# FPGA_Power.net
KiCad netlist of a schematic drawn in Altium Designer
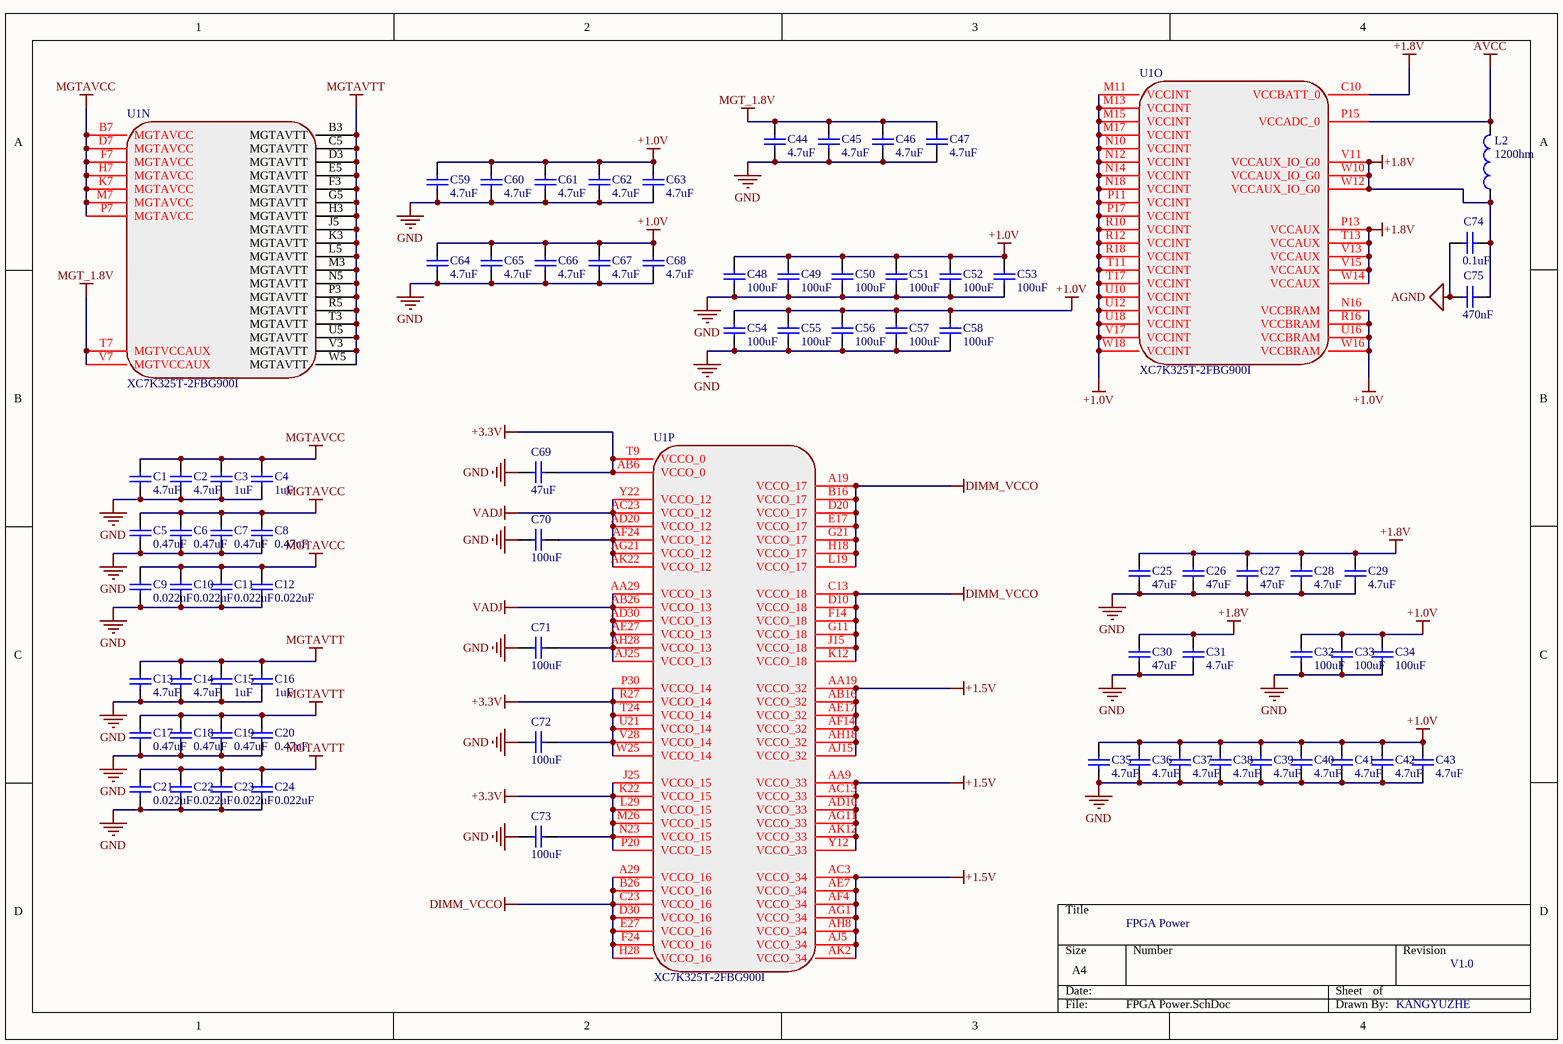
[diagram p0: FPGA Power.SchDoc]

(export (version "E")
  (design (tool "Eeschema 10.0.6"))
  (components
    (comp (ref "C1")
      (value "4.7uF")
      (footprint "0402")
      (description "Capacitor (Semiconductor SIM Model)")
      (fields (field (name "Comment") "Cap Semi") (field (name "PUBLISHER") "Altium Limited"))
      (libsource (lib "Miscellaneous Devices") (part "Cap Semi"))
    )
    (comp (ref "C2")
      (value "4.7uF")
      (footprint "0402")
      (description "Capacitor (Semiconductor SIM Model)")
      (fields (field (name "Comment") "Cap Semi") (field (name "PUBLISHER") "Altium Limited"))
      (libsource (lib "Miscellaneous Devices") (part "Cap Semi"))
    )
    (comp (ref "C3")
      (value "1uF")
      (footprint "0402")
      (description "Capacitor (Semiconductor SIM Model)")
      (fields (field (name "Comment") "Cap Semi") (field (name "PUBLISHER") "Altium Limited"))
      (libsource (lib "Miscellaneous Devices") (part "Cap Semi"))
    )
    (comp (ref "C4")
      (value "1uF")
      (footprint "0402")
      (description "Capacitor (Semiconductor SIM Model)")
      (fields (field (name "Comment") "Cap Semi") (field (name "PUBLISHER") "Altium Limited"))
      (libsource (lib "Miscellaneous Devices") (part "Cap Semi"))
    )
    (comp (ref "C5")
      (value "0.47uF")
      (footprint "0402")
      (description "Capacitor (Semiconductor SIM Model)")
      (fields (field (name "Comment") "Cap Semi") (field (name "PUBLISHER") "Altium Limited"))
      (libsource (lib "Miscellaneous Devices") (part "Cap Semi"))
    )
    (comp (ref "C6")
      (value "0.47uF")
      (footprint "0402")
      (description "Capacitor (Semiconductor SIM Model)")
      (fields (field (name "Comment") "Cap Semi") (field (name "PUBLISHER") "Altium Limited"))
      (libsource (lib "Miscellaneous Devices") (part "Cap Semi"))
    )
    (comp (ref "C7")
      (value "0.47uF")
      (footprint "0402")
      (description "Capacitor (Semiconductor SIM Model)")
      (fields (field (name "Comment") "Cap Semi") (field (name "PUBLISHER") "Altium Limited"))
      (libsource (lib "Miscellaneous Devices") (part "Cap Semi"))
    )
    (comp (ref "C8")
      (value "0.47uF")
      (footprint "0402")
      (description "Capacitor (Semiconductor SIM Model)")
      (fields (field (name "Comment") "Cap Semi") (field (name "PUBLISHER") "Altium Limited"))
      (libsource (lib "Miscellaneous Devices") (part "Cap Semi"))
    )
    (comp (ref "C9")
      (value "0.022uF")
      (footprint "0402")
      (description "Capacitor (Semiconductor SIM Model)")
      (fields (field (name "Comment") "Cap Semi") (field (name "PUBLISHER") "Altium Limited"))
      (libsource (lib "Miscellaneous Devices") (part "Cap Semi"))
    )
    (comp (ref "C10")
      (value "0.022uF")
      (footprint "0402")
      (description "Capacitor (Semiconductor SIM Model)")
      (fields (field (name "Comment") "Cap Semi") (field (name "PUBLISHER") "Altium Limited"))
      (libsource (lib "Miscellaneous Devices") (part "Cap Semi"))
    )
    (comp (ref "C11")
      (value "0.022uF")
      (footprint "0402")
      (description "Capacitor (Semiconductor SIM Model)")
      (fields (field (name "Comment") "Cap Semi") (field (name "PUBLISHER") "Altium Limited"))
      (libsource (lib "Miscellaneous Devices") (part "Cap Semi"))
    )
    (comp (ref "C12")
      (value "0.022uF")
      (footprint "0402")
      (description "Capacitor (Semiconductor SIM Model)")
      (fields (field (name "Comment") "Cap Semi") (field (name "PUBLISHER") "Altium Limited"))
      (libsource (lib "Miscellaneous Devices") (part "Cap Semi"))
    )
    (comp (ref "C13")
      (value "4.7uF")
      (footprint "0402")
      (description "Capacitor (Semiconductor SIM Model)")
      (fields (field (name "Comment") "Cap Semi") (field (name "PUBLISHER") "Altium Limited"))
      (libsource (lib "Miscellaneous Devices") (part "Cap Semi"))
    )
    (comp (ref "C14")
      (value "4.7uF")
      (footprint "0402")
      (description "Capacitor (Semiconductor SIM Model)")
      (fields (field (name "Comment") "Cap Semi") (field (name "PUBLISHER") "Altium Limited"))
      (libsource (lib "Miscellaneous Devices") (part "Cap Semi"))
    )
    (comp (ref "C15")
      (value "1uF")
      (footprint "0402")
      (description "Capacitor (Semiconductor SIM Model)")
      (fields (field (name "Comment") "Cap Semi") (field (name "PUBLISHER") "Altium Limited"))
      (libsource (lib "Miscellaneous Devices") (part "Cap Semi"))
    )
    (comp (ref "C16")
      (value "1uF")
      (footprint "0402")
      (description "Capacitor (Semiconductor SIM Model)")
      (fields (field (name "Comment") "Cap Semi") (field (name "PUBLISHER") "Altium Limited"))
      (libsource (lib "Miscellaneous Devices") (part "Cap Semi"))
    )
    (comp (ref "C17")
      (value "0.47uF")
      (footprint "0402")
      (description "Capacitor (Semiconductor SIM Model)")
      (fields (field (name "Comment") "Cap Semi") (field (name "PUBLISHER") "Altium Limited"))
      (libsource (lib "Miscellaneous Devices") (part "Cap Semi"))
    )
    (comp (ref "C18")
      (value "0.47uF")
      (footprint "0402")
      (description "Capacitor (Semiconductor SIM Model)")
      (fields (field (name "Comment") "Cap Semi") (field (name "PUBLISHER") "Altium Limited"))
      (libsource (lib "Miscellaneous Devices") (part "Cap Semi"))
    )
    (comp (ref "C19")
      (value "0.47uF")
      (footprint "0402")
      (description "Capacitor (Semiconductor SIM Model)")
      (fields (field (name "Comment") "Cap Semi") (field (name "PUBLISHER") "Altium Limited"))
      (libsource (lib "Miscellaneous Devices") (part "Cap Semi"))
    )
    (comp (ref "C20")
      (value "0.47uF")
      (footprint "0402")
      (description "Capacitor (Semiconductor SIM Model)")
      (fields (field (name "Comment") "Cap Semi") (field (name "PUBLISHER") "Altium Limited"))
      (libsource (lib "Miscellaneous Devices") (part "Cap Semi"))
    )
    (comp (ref "C21")
      (value "0.022uF")
      (footprint "0402")
      (description "Capacitor (Semiconductor SIM Model)")
      (fields (field (name "Comment") "Cap Semi") (field (name "PUBLISHER") "Altium Limited"))
      (libsource (lib "Miscellaneous Devices") (part "Cap Semi"))
    )
    (comp (ref "C22")
      (value "0.022uF")
      (footprint "0402")
      (description "Capacitor (Semiconductor SIM Model)")
      (fields (field (name "Comment") "Cap Semi") (field (name "PUBLISHER") "Altium Limited"))
      (libsource (lib "Miscellaneous Devices") (part "Cap Semi"))
    )
    (comp (ref "C23")
      (value "0.022uF")
      (footprint "0402")
      (description "Capacitor (Semiconductor SIM Model)")
      (fields (field (name "Comment") "Cap Semi") (field (name "PUBLISHER") "Altium Limited"))
      (libsource (lib "Miscellaneous Devices") (part "Cap Semi"))
    )
    (comp (ref "C24")
      (value "0.022uF")
      (footprint "0402")
      (description "Capacitor (Semiconductor SIM Model)")
      (fields (field (name "Comment") "Cap Semi") (field (name "PUBLISHER") "Altium Limited"))
      (libsource (lib "Miscellaneous Devices") (part "Cap Semi"))
    )
    (comp (ref "C25")
      (value "47uF")
      (footprint "0402")
      (description "Capacitor (Semiconductor SIM Model)")
      (fields (field (name "Comment") "Cap Semi") (field (name "PUBLISHER") "Altium Limited"))
      (libsource (lib "Miscellaneous Devices") (part "Cap Semi"))
    )
    (comp (ref "C26")
      (value "47uF")
      (footprint "0402")
      (description "Capacitor (Semiconductor SIM Model)")
      (fields (field (name "Comment") "Cap Semi") (field (name "PUBLISHER") "Altium Limited"))
      (libsource (lib "Miscellaneous Devices") (part "Cap Semi"))
    )
    (comp (ref "C27")
      (value "47uF")
      (footprint "0402")
      (description "Capacitor (Semiconductor SIM Model)")
      (fields (field (name "Comment") "Cap Semi") (field (name "PUBLISHER") "Altium Limited"))
      (libsource (lib "Miscellaneous Devices") (part "Cap Semi"))
    )
    (comp (ref "C28")
      (value "4.7uF")
      (footprint "0402")
      (description "Capacitor (Semiconductor SIM Model)")
      (fields (field (name "Comment") "Cap Semi") (field (name "PUBLISHER") "Altium Limited"))
      (libsource (lib "Miscellaneous Devices") (part "Cap Semi"))
    )
    (comp (ref "C29")
      (value "4.7uF")
      (footprint "0402")
      (description "Capacitor (Semiconductor SIM Model)")
      (fields (field (name "Comment") "Cap Semi") (field (name "PUBLISHER") "Altium Limited"))
      (libsource (lib "Miscellaneous Devices") (part "Cap Semi"))
    )
    (comp (ref "C30")
      (value "47uF")
      (footprint "0402")
      (description "Capacitor (Semiconductor SIM Model)")
      (fields (field (name "Comment") "Cap Semi") (field (name "PUBLISHER") "Altium Limited"))
      (libsource (lib "Miscellaneous Devices") (part "Cap Semi"))
    )
    (comp (ref "C31")
      (value "4.7uF")
      (footprint "0402")
      (description "Capacitor (Semiconductor SIM Model)")
      (fields (field (name "Comment") "Cap Semi") (field (name "PUBLISHER") "Altium Limited"))
      (libsource (lib "Miscellaneous Devices") (part "Cap Semi"))
    )
    (comp (ref "C32")
      (value "100uF")
      (footprint "0402")
      (description "Capacitor (Semiconductor SIM Model)")
      (fields (field (name "Comment") "Cap Semi") (field (name "PUBLISHER") "Altium Limited"))
      (libsource (lib "Miscellaneous Devices") (part "Cap Semi"))
    )
    (comp (ref "C33")
      (value "100uF")
      (footprint "0402")
      (description "Capacitor (Semiconductor SIM Model)")
      (fields (field (name "Comment") "Cap Semi") (field (name "PUBLISHER") "Altium Limited"))
      (libsource (lib "Miscellaneous Devices") (part "Cap Semi"))
    )
    (comp (ref "C34")
      (value "100uF")
      (footprint "0402")
      (description "Capacitor (Semiconductor SIM Model)")
      (fields (field (name "Comment") "Cap Semi") (field (name "PUBLISHER") "Altium Limited"))
      (libsource (lib "Miscellaneous Devices") (part "Cap Semi"))
    )
    (comp (ref "C35")
      (value "4.7uF")
      (footprint "0402")
      (description "Capacitor (Semiconductor SIM Model)")
      (fields (field (name "Comment") "Cap Semi") (field (name "PUBLISHER") "Altium Limited"))
      (libsource (lib "Miscellaneous Devices") (part "Cap Semi"))
    )
    (comp (ref "C36")
      (value "4.7uF")
      (footprint "0402")
      (description "Capacitor (Semiconductor SIM Model)")
      (fields (field (name "Comment") "Cap Semi") (field (name "PUBLISHER") "Altium Limited"))
      (libsource (lib "Miscellaneous Devices") (part "Cap Semi"))
    )
    (comp (ref "C37")
      (value "4.7uF")
      (footprint "0402")
      (description "Capacitor (Semiconductor SIM Model)")
      (fields (field (name "Comment") "Cap Semi") (field (name "PUBLISHER") "Altium Limited"))
      (libsource (lib "Miscellaneous Devices") (part "Cap Semi"))
    )
    (comp (ref "C38")
      (value "4.7uF")
      (footprint "0402")
      (description "Capacitor (Semiconductor SIM Model)")
      (fields (field (name "Comment") "Cap Semi") (field (name "PUBLISHER") "Altium Limited"))
      (libsource (lib "Miscellaneous Devices") (part "Cap Semi"))
    )
    (comp (ref "C39")
      (value "4.7uF")
      (footprint "0402")
      (description "Capacitor (Semiconductor SIM Model)")
      (fields (field (name "Comment") "Cap Semi") (field (name "PUBLISHER") "Altium Limited"))
      (libsource (lib "Miscellaneous Devices") (part "Cap Semi"))
    )
    (comp (ref "C40")
      (value "4.7uF")
      (footprint "0402")
      (description "Capacitor (Semiconductor SIM Model)")
      (fields (field (name "Comment") "Cap Semi") (field (name "PUBLISHER") "Altium Limited"))
      (libsource (lib "Miscellaneous Devices") (part "Cap Semi"))
    )
    (comp (ref "C41")
      (value "4.7uF")
      (footprint "0402")
      (description "Capacitor (Semiconductor SIM Model)")
      (fields (field (name "Comment") "Cap Semi") (field (name "PUBLISHER") "Altium Limited"))
      (libsource (lib "Miscellaneous Devices") (part "Cap Semi"))
    )
    (comp (ref "C42")
      (value "4.7uF")
      (footprint "0402")
      (description "Capacitor (Semiconductor SIM Model)")
      (fields (field (name "Comment") "Cap Semi") (field (name "PUBLISHER") "Altium Limited"))
      (libsource (lib "Miscellaneous Devices") (part "Cap Semi"))
    )
    (comp (ref "C43")
      (value "4.7uF")
      (footprint "0402")
      (description "Capacitor (Semiconductor SIM Model)")
      (fields (field (name "Comment") "Cap Semi") (field (name "PUBLISHER") "Altium Limited"))
      (libsource (lib "Miscellaneous Devices") (part "Cap Semi"))
    )
    (comp (ref "C44")
      (value "4.7uF")
      (footprint "0402")
      (description "Capacitor (Semiconductor SIM Model)")
      (fields (field (name "Comment") "Cap Semi") (field (name "PUBLISHER") "Altium Limited"))
      (libsource (lib "Miscellaneous Devices") (part "Cap Semi"))
    )
    (comp (ref "C45")
      (value "4.7uF")
      (footprint "0402")
      (description "Capacitor (Semiconductor SIM Model)")
      (fields (field (name "Comment") "Cap Semi") (field (name "PUBLISHER") "Altium Limited"))
      (libsource (lib "Miscellaneous Devices") (part "Cap Semi"))
    )
    (comp (ref "C46")
      (value "4.7uF")
      (footprint "0402")
      (description "Capacitor (Semiconductor SIM Model)")
      (fields (field (name "Comment") "Cap Semi") (field (name "PUBLISHER") "Altium Limited"))
      (libsource (lib "Miscellaneous Devices") (part "Cap Semi"))
    )
    (comp (ref "C47")
      (value "4.7uF")
      (footprint "0402")
      (description "Capacitor (Semiconductor SIM Model)")
      (fields (field (name "Comment") "Cap Semi") (field (name "PUBLISHER") "Altium Limited"))
      (libsource (lib "Miscellaneous Devices") (part "Cap Semi"))
    )
    (comp (ref "C48")
      (value "100uF")
      (footprint "0402")
      (description "Capacitor (Semiconductor SIM Model)")
      (fields (field (name "Comment") "Cap Semi") (field (name "PUBLISHER") "Altium Limited"))
      (libsource (lib "Miscellaneous Devices") (part "Cap Semi"))
    )
    (comp (ref "C49")
      (value "100uF")
      (footprint "0402")
      (description "Capacitor (Semiconductor SIM Model)")
      (fields (field (name "Comment") "Cap Semi") (field (name "PUBLISHER") "Altium Limited"))
      (libsource (lib "Miscellaneous Devices") (part "Cap Semi"))
    )
    (comp (ref "C50")
      (value "100uF")
      (footprint "0402")
      (description "Capacitor (Semiconductor SIM Model)")
      (fields (field (name "Comment") "Cap Semi") (field (name "PUBLISHER") "Altium Limited"))
      (libsource (lib "Miscellaneous Devices") (part "Cap Semi"))
    )
    (comp (ref "C51")
      (value "100uF")
      (footprint "0402")
      (description "Capacitor (Semiconductor SIM Model)")
      (fields (field (name "Comment") "Cap Semi") (field (name "PUBLISHER") "Altium Limited"))
      (libsource (lib "Miscellaneous Devices") (part "Cap Semi"))
    )
    (comp (ref "C52")
      (value "100uF")
      (footprint "0402")
      (description "Capacitor (Semiconductor SIM Model)")
      (fields (field (name "Comment") "Cap Semi") (field (name "PUBLISHER") "Altium Limited"))
      (libsource (lib "Miscellaneous Devices") (part "Cap Semi"))
    )
    (comp (ref "C53")
      (value "100uF")
      (footprint "0402")
      (description "Capacitor (Semiconductor SIM Model)")
      (fields (field (name "Comment") "Cap Semi") (field (name "PUBLISHER") "Altium Limited"))
      (libsource (lib "Miscellaneous Devices") (part "Cap Semi"))
    )
    (comp (ref "C54")
      (value "100uF")
      (footprint "0402")
      (description "Capacitor (Semiconductor SIM Model)")
      (fields (field (name "Comment") "Cap Semi") (field (name "PUBLISHER") "Altium Limited"))
      (libsource (lib "Miscellaneous Devices") (part "Cap Semi"))
    )
    (comp (ref "C55")
      (value "100uF")
      (footprint "0402")
      (description "Capacitor (Semiconductor SIM Model)")
      (fields (field (name "Comment") "Cap Semi") (field (name "PUBLISHER") "Altium Limited"))
      (libsource (lib "Miscellaneous Devices") (part "Cap Semi"))
    )
    (comp (ref "C56")
      (value "100uF")
      (footprint "0402")
      (description "Capacitor (Semiconductor SIM Model)")
      (fields (field (name "Comment") "Cap Semi") (field (name "PUBLISHER") "Altium Limited"))
      (libsource (lib "Miscellaneous Devices") (part "Cap Semi"))
    )
    (comp (ref "C57")
      (value "100uF")
      (footprint "0402")
      (description "Capacitor (Semiconductor SIM Model)")
      (fields (field (name "Comment") "Cap Semi") (field (name "PUBLISHER") "Altium Limited"))
      (libsource (lib "Miscellaneous Devices") (part "Cap Semi"))
    )
    (comp (ref "C58")
      (value "100uF")
      (footprint "0402")
      (description "Capacitor (Semiconductor SIM Model)")
      (fields (field (name "Comment") "Cap Semi") (field (name "PUBLISHER") "Altium Limited"))
      (libsource (lib "Miscellaneous Devices") (part "Cap Semi"))
    )
    (comp (ref "C59")
      (value "4.7uF")
      (footprint "0402")
      (description "Capacitor (Semiconductor SIM Model)")
      (fields (field (name "Comment") "Cap Semi") (field (name "PUBLISHER") "Altium Limited"))
      (libsource (lib "Miscellaneous Devices") (part "Cap Semi"))
    )
    (comp (ref "C60")
      (value "4.7uF")
      (footprint "0402")
      (description "Capacitor (Semiconductor SIM Model)")
      (fields (field (name "Comment") "Cap Semi") (field (name "PUBLISHER") "Altium Limited"))
      (libsource (lib "Miscellaneous Devices") (part "Cap Semi"))
    )
    (comp (ref "C61")
      (value "4.7uF")
      (footprint "0402")
      (description "Capacitor (Semiconductor SIM Model)")
      (fields (field (name "Comment") "Cap Semi") (field (name "PUBLISHER") "Altium Limited"))
      (libsource (lib "Miscellaneous Devices") (part "Cap Semi"))
    )
    (comp (ref "C62")
      (value "4.7uF")
      (footprint "0402")
      (description "Capacitor (Semiconductor SIM Model)")
      (fields (field (name "Comment") "Cap Semi") (field (name "PUBLISHER") "Altium Limited"))
      (libsource (lib "Miscellaneous Devices") (part "Cap Semi"))
    )
    (comp (ref "C63")
      (value "4.7uF")
      (footprint "0402")
      (description "Capacitor (Semiconductor SIM Model)")
      (fields (field (name "Comment") "Cap Semi") (field (name "PUBLISHER") "Altium Limited"))
      (libsource (lib "Miscellaneous Devices") (part "Cap Semi"))
    )
    (comp (ref "C64")
      (value "4.7uF")
      (footprint "0402")
      (description "Capacitor (Semiconductor SIM Model)")
      (fields (field (name "Comment") "Cap Semi") (field (name "PUBLISHER") "Altium Limited"))
      (libsource (lib "Miscellaneous Devices") (part "Cap Semi"))
    )
    (comp (ref "C65")
      (value "4.7uF")
      (footprint "0402")
      (description "Capacitor (Semiconductor SIM Model)")
      (fields (field (name "Comment") "Cap Semi") (field (name "PUBLISHER") "Altium Limited"))
      (libsource (lib "Miscellaneous Devices") (part "Cap Semi"))
    )
    (comp (ref "C66")
      (value "4.7uF")
      (footprint "0402")
      (description "Capacitor (Semiconductor SIM Model)")
      (fields (field (name "Comment") "Cap Semi") (field (name "PUBLISHER") "Altium Limited"))
      (libsource (lib "Miscellaneous Devices") (part "Cap Semi"))
    )
    (comp (ref "C67")
      (value "4.7uF")
      (footprint "0402")
      (description "Capacitor (Semiconductor SIM Model)")
      (fields (field (name "Comment") "Cap Semi") (field (name "PUBLISHER") "Altium Limited"))
      (libsource (lib "Miscellaneous Devices") (part "Cap Semi"))
    )
    (comp (ref "C68")
      (value "4.7uF")
      (footprint "0402")
      (description "Capacitor (Semiconductor SIM Model)")
      (fields (field (name "Comment") "Cap Semi") (field (name "PUBLISHER") "Altium Limited"))
      (libsource (lib "Miscellaneous Devices") (part "Cap Semi"))
    )
    (comp (ref "C69")
      (value "47uF")
      (footprint "0402")
      (description "Capacitor (Semiconductor SIM Model)")
      (fields (field (name "Comment") "Cap Semi") (field (name "PUBLISHER") "Altium Limited"))
      (libsource (lib "Miscellaneous Devices") (part "Cap Semi"))
    )
    (comp (ref "C70")
      (value "100uF")
      (footprint "0402")
      (description "Capacitor (Semiconductor SIM Model)")
      (fields (field (name "Comment") "Cap Semi") (field (name "PUBLISHER") "Altium Limited"))
      (libsource (lib "Miscellaneous Devices") (part "Cap Semi"))
    )
    (comp (ref "C71")
      (value "100uF")
      (footprint "0402")
      (description "Capacitor (Semiconductor SIM Model)")
      (fields (field (name "Comment") "Cap Semi") (field (name "PUBLISHER") "Altium Limited"))
      (libsource (lib "Miscellaneous Devices") (part "Cap Semi"))
    )
    (comp (ref "C72")
      (value "100uF")
      (footprint "0402")
      (description "Capacitor (Semiconductor SIM Model)")
      (fields (field (name "Comment") "Cap Semi") (field (name "PUBLISHER") "Altium Limited"))
      (libsource (lib "Miscellaneous Devices") (part "Cap Semi"))
    )
    (comp (ref "C73")
      (value "100uF")
      (footprint "0402")
      (description "Capacitor (Semiconductor SIM Model)")
      (fields (field (name "Comment") "Cap Semi") (field (name "PUBLISHER") "Altium Limited"))
      (libsource (lib "Miscellaneous Devices") (part "Cap Semi"))
    )
    (comp (ref "C74")
      (value "0.1uF")
      (footprint "0402")
      (description "Capacitor (Semiconductor SIM Model)")
      (fields (field (name "Comment") "Cap Semi") (field (name "PUBLISHER") "Altium Limited"))
      (libsource (lib "Miscellaneous Devices") (part "Cap Semi"))
    )
    (comp (ref "C75")
      (value "470nF")
      (footprint "0402")
      (description "Capacitor (Semiconductor SIM Model)")
      (fields (field (name "Comment") "Cap Semi") (field (name "PUBLISHER") "Altium Limited"))
      (libsource (lib "Miscellaneous Devices") (part "Cap Semi"))
    )
    (comp (ref "L2")
      (value "1200hm")
      (footprint "0402-A")
      (description "Inductor")
      (fields (field (name "PUBLISHER") "Altium Limited"))
      (libsource (lib "Miscellaneous Devices") (part "Inductor"))
    )
    (comp (ref "U1") (value "XC7K325T-2FBG900I") (libsource (lib "Schlib1") (part "XC7K325T-2FBG900I")))
  )
  (nets
    (net (code "1") (name "+1.0V") (class "Default")
      (node (ref "C32") (pin "2") (pinfunction "2_2") (pintype "passive"))
      (node (ref "C33") (pin "2") (pinfunction "2_2") (pintype "passive"))
      (node (ref "C34") (pin "2") (pinfunction "2_2") (pintype "passive"))
      (node (ref "C35") (pin "2") (pinfunction "2_2") (pintype "passive"))
      (node (ref "C36") (pin "2") (pinfunction "2_2") (pintype "passive"))
      (node (ref "C37") (pin "2") (pinfunction "2_2") (pintype "passive"))
      (node (ref "C38") (pin "2") (pinfunction "2_2") (pintype "passive"))
      (node (ref "C39") (pin "2") (pinfunction "2_2") (pintype "passive"))
      (node (ref "C40") (pin "2") (pinfunction "2_2") (pintype "passive"))
      (node (ref "C41") (pin "2") (pinfunction "2_2") (pintype "passive"))
      (node (ref "C42") (pin "2") (pinfunction "2_2") (pintype "passive"))
      (node (ref "C43") (pin "2") (pinfunction "2_2") (pintype "passive"))
      (node (ref "C48") (pin "2") (pinfunction "2_2") (pintype "passive"))
      (node (ref "C49") (pin "2") (pinfunction "2_2") (pintype "passive"))
      (node (ref "C50") (pin "2") (pinfunction "2_2") (pintype "passive"))
      (node (ref "C51") (pin "2") (pinfunction "2_2") (pintype "passive"))
      (node (ref "C52") (pin "2") (pinfunction "2_2") (pintype "passive"))
      (node (ref "C53") (pin "2") (pinfunction "2_2") (pintype "passive"))
      (node (ref "C54") (pin "2") (pinfunction "2_2") (pintype "passive"))
      (node (ref "C55") (pin "2") (pinfunction "2_2") (pintype "passive"))
      (node (ref "C56") (pin "2") (pinfunction "2_2") (pintype "passive"))
      (node (ref "C57") (pin "2") (pinfunction "2_2") (pintype "passive"))
      (node (ref "C58") (pin "2") (pinfunction "2_2") (pintype "passive"))
      (node (ref "C59") (pin "2") (pinfunction "2_2") (pintype "passive"))
      (node (ref "C60") (pin "2") (pinfunction "2_2") (pintype "passive"))
      (node (ref "C61") (pin "2") (pinfunction "2_2") (pintype "passive"))
      (node (ref "C62") (pin "2") (pinfunction "2_2") (pintype "passive"))
      (node (ref "C63") (pin "2") (pinfunction "2_2") (pintype "passive"))
      (node (ref "C64") (pin "2") (pinfunction "2_2") (pintype "passive"))
      (node (ref "C65") (pin "2") (pinfunction "2_2") (pintype "passive"))
      (node (ref "C66") (pin "2") (pinfunction "2_2") (pintype "passive"))
      (node (ref "C67") (pin "2") (pinfunction "2_2") (pintype "passive"))
      (node (ref "C68") (pin "2") (pinfunction "2_2") (pintype "passive"))
      (node (ref "U1") (pin "M11") (pinfunction "VCCINT_M11") (pintype "passive"))
      (node (ref "U1") (pin "M13") (pinfunction "VCCINT_M13") (pintype "passive"))
      (node (ref "U1") (pin "M15") (pinfunction "VCCINT_M15") (pintype "passive"))
      (node (ref "U1") (pin "M17") (pinfunction "VCCINT_M17") (pintype "passive"))
      (node (ref "U1") (pin "N10") (pinfunction "VCCINT_N10") (pintype "passive"))
      (node (ref "U1") (pin "N12") (pinfunction "VCCINT_N12") (pintype "passive"))
      (node (ref "U1") (pin "N14") (pinfunction "VCCINT_N14") (pintype "passive"))
      (node (ref "U1") (pin "N16") (pinfunction "VCCBRAM_N16") (pintype "passive"))
      (node (ref "U1") (pin "N18") (pinfunction "VCCINT_N18") (pintype "passive"))
      (node (ref "U1") (pin "P11") (pinfunction "VCCINT_P11") (pintype "passive"))
      (node (ref "U1") (pin "P17") (pinfunction "VCCINT_P17") (pintype "passive"))
      (node (ref "U1") (pin "R10") (pinfunction "VCCINT_R10") (pintype "passive"))
      (node (ref "U1") (pin "R12") (pinfunction "VCCINT_R12") (pintype "passive"))
      (node (ref "U1") (pin "R16") (pinfunction "VCCBRAM_R16") (pintype "passive"))
      (node (ref "U1") (pin "R18") (pinfunction "VCCINT_R18") (pintype "passive"))
      (node (ref "U1") (pin "T11") (pinfunction "VCCINT_T11") (pintype "passive"))
      (node (ref "U1") (pin "T17") (pinfunction "VCCINT_T17") (pintype "passive"))
      (node (ref "U1") (pin "U10") (pinfunction "VCCINT_U10") (pintype "passive"))
      (node (ref "U1") (pin "U12") (pinfunction "VCCINT_U12") (pintype "passive"))
      (node (ref "U1") (pin "U16") (pinfunction "VCCBRAM_U16") (pintype "passive"))
      (node (ref "U1") (pin "U18") (pinfunction "VCCINT_U18") (pintype "passive"))
      (node (ref "U1") (pin "V17") (pinfunction "VCCINT_V17") (pintype "passive"))
      (node (ref "U1") (pin "W16") (pinfunction "VCCBRAM_W16") (pintype "passive"))
      (node (ref "U1") (pin "W18") (pinfunction "VCCINT_W18") (pintype "passive"))
    )
    (net (code "2") (name "+1.5V") (class "Default")
      (node (ref "U1") (pin "AA19") (pinfunction "VCCO_32_AA19") (pintype "passive"))
      (node (ref "U1") (pin "AA9") (pinfunction "VCCO_33_AA9") (pintype "passive"))
      (node (ref "U1") (pin "AB16") (pinfunction "VCCO_32_AB16") (pintype "passive"))
      (node (ref "U1") (pin "AC13") (pinfunction "VCCO_33_AC13") (pintype "passive"))
      (node (ref "U1") (pin "AC3") (pinfunction "VCCO_34_AC3") (pintype "passive"))
      (node (ref "U1") (pin "AD10") (pinfunction "VCCO_33_AD10") (pintype "passive"))
      (node (ref "U1") (pin "AE17") (pinfunction "VCCO_32_AE17") (pintype "passive"))
      (node (ref "U1") (pin "AE7") (pinfunction "VCCO_34_AE7") (pintype "passive"))
      (node (ref "U1") (pin "AF14") (pinfunction "VCCO_32_AF14") (pintype "passive"))
      (node (ref "U1") (pin "AF4") (pinfunction "VCCO_34_AF4") (pintype "passive"))
      (node (ref "U1") (pin "AG1") (pinfunction "VCCO_34_AG1") (pintype "passive"))
      (node (ref "U1") (pin "AG11") (pinfunction "VCCO_33_AG11") (pintype "passive"))
      (node (ref "U1") (pin "AH18") (pinfunction "VCCO_32_AH18") (pintype "passive"))
      (node (ref "U1") (pin "AH8") (pinfunction "VCCO_34_AH8") (pintype "passive"))
      (node (ref "U1") (pin "AJ15") (pinfunction "VCCO_32_AJ15") (pintype "passive"))
      (node (ref "U1") (pin "AJ5") (pinfunction "VCCO_34_AJ5") (pintype "passive"))
      (node (ref "U1") (pin "AK12") (pinfunction "VCCO_33_AK12") (pintype "passive"))
      (node (ref "U1") (pin "AK2") (pinfunction "VCCO_34_AK2") (pintype "passive"))
      (node (ref "U1") (pin "Y12") (pinfunction "VCCO_33_Y12") (pintype "passive"))
    )
    (net (code "3") (name "+1.8V") (class "Default")
      (node (ref "C25") (pin "2") (pinfunction "2_2") (pintype "passive"))
      (node (ref "C26") (pin "2") (pinfunction "2_2") (pintype "passive"))
      (node (ref "C27") (pin "2") (pinfunction "2_2") (pintype "passive"))
      (node (ref "C28") (pin "2") (pinfunction "2_2") (pintype "passive"))
      (node (ref "C29") (pin "2") (pinfunction "2_2") (pintype "passive"))
      (node (ref "C30") (pin "2") (pinfunction "2_2") (pintype "passive"))
      (node (ref "C31") (pin "2") (pinfunction "2_2") (pintype "passive"))
      (node (ref "C74") (pin "2") (pinfunction "2_2") (pintype "passive"))
      (node (ref "C75") (pin "2") (pinfunction "2_2") (pintype "passive"))
      (node (ref "L2") (pin "1") (pinfunction "1_1") (pintype "passive"))
      (node (ref "U1") (pin "C10") (pinfunction "VCCBATT_0_C10") (pintype "passive"))
      (node (ref "U1") (pin "P13") (pinfunction "VCCAUX_P13") (pintype "passive"))
      (node (ref "U1") (pin "T13") (pinfunction "VCCAUX_T13") (pintype "passive"))
      (node (ref "U1") (pin "V11") (pinfunction "VCCAUX_IO_G0_V11") (pintype "passive"))
      (node (ref "U1") (pin "V13") (pinfunction "VCCAUX_V13") (pintype "passive"))
      (node (ref "U1") (pin "V15") (pinfunction "VCCAUX_V15") (pintype "passive"))
      (node (ref "U1") (pin "W10") (pinfunction "VCCAUX_IO_G0_W10") (pintype "passive"))
      (node (ref "U1") (pin "W12") (pinfunction "VCCAUX_IO_G0_W12") (pintype "passive"))
      (node (ref "U1") (pin "W14") (pinfunction "VCCAUX_W14") (pintype "passive"))
    )
    (net (code "4") (name "+3.3V") (class "Default")
      (node (ref "C69") (pin "2") (pinfunction "2_2") (pintype "passive"))
      (node (ref "C72") (pin "2") (pinfunction "2_2") (pintype "passive"))
      (node (ref "C73") (pin "2") (pinfunction "2_2") (pintype "passive"))
      (node (ref "U1") (pin "AB6") (pinfunction "VCCO_0_AB6") (pintype "passive"))
      (node (ref "U1") (pin "J25") (pinfunction "VCCO_15_J25") (pintype "passive"))
      (node (ref "U1") (pin "K22") (pinfunction "VCCO_15_K22") (pintype "passive"))
      (node (ref "U1") (pin "L29") (pinfunction "VCCO_15_L29") (pintype "passive"))
      (node (ref "U1") (pin "M26") (pinfunction "VCCO_15_M26") (pintype "passive"))
      (node (ref "U1") (pin "N23") (pinfunction "VCCO_15_N23") (pintype "passive"))
      (node (ref "U1") (pin "P20") (pinfunction "VCCO_15_P20") (pintype "passive"))
      (node (ref "U1") (pin "P30") (pinfunction "VCCO_14_P30") (pintype "passive"))
      (node (ref "U1") (pin "R27") (pinfunction "VCCO_14_R27") (pintype "passive"))
      (node (ref "U1") (pin "T24") (pinfunction "VCCO_14_T24") (pintype "passive"))
      (node (ref "U1") (pin "T9") (pinfunction "VCCO_0_T9") (pintype "passive"))
      (node (ref "U1") (pin "U21") (pinfunction "VCCO_14_U21") (pintype "passive"))
      (node (ref "U1") (pin "V28") (pinfunction "VCCO_14_V28") (pintype "passive"))
      (node (ref "U1") (pin "W25") (pinfunction "VCCO_14_W25") (pintype "passive"))
    )
    (net (code "5") (name "AGND") (class "Default")
      (node (ref "C74") (pin "1") (pinfunction "1_1") (pintype "passive"))
      (node (ref "C75") (pin "1") (pinfunction "1_1") (pintype "passive"))
    )
    (net (code "6") (name "AVCC") (class "Default")
      (node (ref "L2") (pin "2") (pinfunction "2_2") (pintype "passive"))
      (node (ref "U1") (pin "P15") (pinfunction "VCCADC_0_P15") (pintype "passive"))
    )
    (net (code "7") (name "DIMM_VCCO") (class "Default")
      (node (ref "U1") (pin "A19") (pinfunction "VCCO_17_A19") (pintype "passive"))
      (node (ref "U1") (pin "A29") (pinfunction "VCCO_16_A29") (pintype "passive"))
      (node (ref "U1") (pin "B16") (pinfunction "VCCO_17_B16") (pintype "passive"))
      (node (ref "U1") (pin "B26") (pinfunction "VCCO_16_B26") (pintype "passive"))
      (node (ref "U1") (pin "C13") (pinfunction "VCCO_18_C13") (pintype "passive"))
      (node (ref "U1") (pin "C23") (pinfunction "VCCO_16_C23") (pintype "passive"))
      (node (ref "U1") (pin "D10") (pinfunction "VCCO_18_D10") (pintype "passive"))
      (node (ref "U1") (pin "D20") (pinfunction "VCCO_17_D20") (pintype "passive"))
      (node (ref "U1") (pin "D30") (pinfunction "VCCO_16_D30") (pintype "passive"))
      (node (ref "U1") (pin "E17") (pinfunction "VCCO_17_E17") (pintype "passive"))
      (node (ref "U1") (pin "E27") (pinfunction "VCCO_16_E27") (pintype "passive"))
      (node (ref "U1") (pin "F14") (pinfunction "VCCO_18_F14") (pintype "passive"))
      (node (ref "U1") (pin "F24") (pinfunction "VCCO_16_F24") (pintype "passive"))
      (node (ref "U1") (pin "G11") (pinfunction "VCCO_18_G11") (pintype "passive"))
      (node (ref "U1") (pin "G21") (pinfunction "VCCO_17_G21") (pintype "passive"))
      (node (ref "U1") (pin "H18") (pinfunction "VCCO_17_H18") (pintype "passive"))
      (node (ref "U1") (pin "H28") (pinfunction "VCCO_16_H28") (pintype "passive"))
      (node (ref "U1") (pin "J15") (pinfunction "VCCO_18_J15") (pintype "passive"))
      (node (ref "U1") (pin "K12") (pinfunction "VCCO_18_K12") (pintype "passive"))
      (node (ref "U1") (pin "L19") (pinfunction "VCCO_17_L19") (pintype "passive"))
    )
    (net (code "8") (name "GND") (class "Default")
      (node (ref "C1") (pin "2") (pinfunction "2_2") (pintype "passive"))
      (node (ref "C10") (pin "1") (pinfunction "1_1") (pintype "passive"))
      (node (ref "C11") (pin "1") (pinfunction "1_1") (pintype "passive"))
      (node (ref "C12") (pin "1") (pinfunction "1_1") (pintype "passive"))
      (node (ref "C13") (pin "2") (pinfunction "2_2") (pintype "passive"))
      (node (ref "C14") (pin "1") (pinfunction "1_1") (pintype "passive"))
      (node (ref "C15") (pin "1") (pinfunction "1_1") (pintype "passive"))
      (node (ref "C16") (pin "1") (pinfunction "1_1") (pintype "passive"))
      (node (ref "C17") (pin "1") (pinfunction "1_1") (pintype "passive"))
      (node (ref "C18") (pin "1") (pinfunction "1_1") (pintype "passive"))
      (node (ref "C19") (pin "1") (pinfunction "1_1") (pintype "passive"))
      (node (ref "C2") (pin "1") (pinfunction "1_1") (pintype "passive"))
      (node (ref "C20") (pin "1") (pinfunction "1_1") (pintype "passive"))
      (node (ref "C21") (pin "1") (pinfunction "1_1") (pintype "passive"))
      (node (ref "C22") (pin "1") (pinfunction "1_1") (pintype "passive"))
      (node (ref "C23") (pin "1") (pinfunction "1_1") (pintype "passive"))
      (node (ref "C24") (pin "1") (pinfunction "1_1") (pintype "passive"))
      (node (ref "C25") (pin "1") (pinfunction "1_1") (pintype "passive"))
      (node (ref "C26") (pin "1") (pinfunction "1_1") (pintype "passive"))
      (node (ref "C27") (pin "1") (pinfunction "1_1") (pintype "passive"))
      (node (ref "C28") (pin "1") (pinfunction "1_1") (pintype "passive"))
      (node (ref "C29") (pin "1") (pinfunction "1_1") (pintype "passive"))
      (node (ref "C3") (pin "1") (pinfunction "1_1") (pintype "passive"))
      (node (ref "C30") (pin "1") (pinfunction "1_1") (pintype "passive"))
      (node (ref "C31") (pin "1") (pinfunction "1_1") (pintype "passive"))
      (node (ref "C32") (pin "1") (pinfunction "1_1") (pintype "passive"))
      (node (ref "C33") (pin "1") (pinfunction "1_1") (pintype "passive"))
      (node (ref "C34") (pin "1") (pinfunction "1_1") (pintype "passive"))
      (node (ref "C35") (pin "1") (pinfunction "1_1") (pintype "passive"))
      (node (ref "C36") (pin "1") (pinfunction "1_1") (pintype "passive"))
      (node (ref "C37") (pin "1") (pinfunction "1_1") (pintype "passive"))
      (node (ref "C38") (pin "1") (pinfunction "1_1") (pintype "passive"))
      (node (ref "C39") (pin "1") (pinfunction "1_1") (pintype "passive"))
      (node (ref "C4") (pin "1") (pinfunction "1_1") (pintype "passive"))
      (node (ref "C40") (pin "1") (pinfunction "1_1") (pintype "passive"))
      (node (ref "C41") (pin "1") (pinfunction "1_1") (pintype "passive"))
      (node (ref "C42") (pin "1") (pinfunction "1_1") (pintype "passive"))
      (node (ref "C43") (pin "1") (pinfunction "1_1") (pintype "passive"))
      (node (ref "C44") (pin "1") (pinfunction "1_1") (pintype "passive"))
      (node (ref "C45") (pin "1") (pinfunction "1_1") (pintype "passive"))
      (node (ref "C46") (pin "1") (pinfunction "1_1") (pintype "passive"))
      (node (ref "C47") (pin "1") (pinfunction "1_1") (pintype "passive"))
      (node (ref "C48") (pin "1") (pinfunction "1_1") (pintype "passive"))
      (node (ref "C49") (pin "1") (pinfunction "1_1") (pintype "passive"))
      (node (ref "C5") (pin "1") (pinfunction "1_1") (pintype "passive"))
      (node (ref "C50") (pin "1") (pinfunction "1_1") (pintype "passive"))
      (node (ref "C51") (pin "1") (pinfunction "1_1") (pintype "passive"))
      (node (ref "C52") (pin "1") (pinfunction "1_1") (pintype "passive"))
      (node (ref "C53") (pin "1") (pinfunction "1_1") (pintype "passive"))
      (node (ref "C54") (pin "1") (pinfunction "1_1") (pintype "passive"))
      (node (ref "C55") (pin "1") (pinfunction "1_1") (pintype "passive"))
      (node (ref "C56") (pin "1") (pinfunction "1_1") (pintype "passive"))
      (node (ref "C57") (pin "1") (pinfunction "1_1") (pintype "passive"))
      (node (ref "C58") (pin "1") (pinfunction "1_1") (pintype "passive"))
      (node (ref "C59") (pin "1") (pinfunction "1_1") (pintype "passive"))
      (node (ref "C6") (pin "1") (pinfunction "1_1") (pintype "passive"))
      (node (ref "C60") (pin "1") (pinfunction "1_1") (pintype "passive"))
      (node (ref "C61") (pin "1") (pinfunction "1_1") (pintype "passive"))
      (node (ref "C62") (pin "1") (pinfunction "1_1") (pintype "passive"))
      (node (ref "C63") (pin "1") (pinfunction "1_1") (pintype "passive"))
      (node (ref "C64") (pin "1") (pinfunction "1_1") (pintype "passive"))
      (node (ref "C65") (pin "1") (pinfunction "1_1") (pintype "passive"))
      (node (ref "C66") (pin "1") (pinfunction "1_1") (pintype "passive"))
      (node (ref "C67") (pin "1") (pinfunction "1_1") (pintype "passive"))
      (node (ref "C68") (pin "1") (pinfunction "1_1") (pintype "passive"))
      (node (ref "C69") (pin "1") (pinfunction "1_1") (pintype "passive"))
      (node (ref "C7") (pin "1") (pinfunction "1_1") (pintype "passive"))
      (node (ref "C70") (pin "1") (pinfunction "1_1") (pintype "passive"))
      (node (ref "C71") (pin "1") (pinfunction "1_1") (pintype "passive"))
      (node (ref "C72") (pin "1") (pinfunction "1_1") (pintype "passive"))
      (node (ref "C73") (pin "1") (pinfunction "1_1") (pintype "passive"))
      (node (ref "C8") (pin "1") (pinfunction "1_1") (pintype "passive"))
      (node (ref "C9") (pin "1") (pinfunction "1_1") (pintype "passive"))
    )
    (net (code "9") (name "MGTAVCC") (class "Default")
      (node (ref "C1") (pin "1") (pinfunction "1_1") (pintype "passive"))
      (node (ref "C10") (pin "2") (pinfunction "2_2") (pintype "passive"))
      (node (ref "C11") (pin "2") (pinfunction "2_2") (pintype "passive"))
      (node (ref "C12") (pin "2") (pinfunction "2_2") (pintype "passive"))
      (node (ref "C2") (pin "2") (pinfunction "2_2") (pintype "passive"))
      (node (ref "C3") (pin "2") (pinfunction "2_2") (pintype "passive"))
      (node (ref "C4") (pin "2") (pinfunction "2_2") (pintype "passive"))
      (node (ref "C5") (pin "2") (pinfunction "2_2") (pintype "passive"))
      (node (ref "C6") (pin "2") (pinfunction "2_2") (pintype "passive"))
      (node (ref "C7") (pin "2") (pinfunction "2_2") (pintype "passive"))
      (node (ref "C8") (pin "2") (pinfunction "2_2") (pintype "passive"))
      (node (ref "C9") (pin "2") (pinfunction "2_2") (pintype "passive"))
      (node (ref "U1") (pin "B7") (pinfunction "MGTAVCC_B7") (pintype "passive"))
      (node (ref "U1") (pin "D7") (pinfunction "MGTAVCC_D7") (pintype "passive"))
      (node (ref "U1") (pin "F7") (pinfunction "MGTAVCC_F7") (pintype "passive"))
      (node (ref "U1") (pin "H7") (pinfunction "MGTAVCC_H7") (pintype "passive"))
      (node (ref "U1") (pin "K7") (pinfunction "MGTAVCC_K7") (pintype "passive"))
      (node (ref "U1") (pin "M7") (pinfunction "MGTAVCC_M7") (pintype "passive"))
      (node (ref "U1") (pin "P7") (pinfunction "MGTAVCC_P7") (pintype "passive"))
    )
    (net (code "10") (name "MGTAVTT") (class "Default")
      (node (ref "C13") (pin "1") (pinfunction "1_1") (pintype "passive"))
      (node (ref "C14") (pin "2") (pinfunction "2_2") (pintype "passive"))
      (node (ref "C15") (pin "2") (pinfunction "2_2") (pintype "passive"))
      (node (ref "C16") (pin "2") (pinfunction "2_2") (pintype "passive"))
      (node (ref "C17") (pin "2") (pinfunction "2_2") (pintype "passive"))
      (node (ref "C18") (pin "2") (pinfunction "2_2") (pintype "passive"))
      (node (ref "C19") (pin "2") (pinfunction "2_2") (pintype "passive"))
      (node (ref "C20") (pin "2") (pinfunction "2_2") (pintype "passive"))
      (node (ref "C21") (pin "2") (pinfunction "2_2") (pintype "passive"))
      (node (ref "C22") (pin "2") (pinfunction "2_2") (pintype "passive"))
      (node (ref "C23") (pin "2") (pinfunction "2_2") (pintype "passive"))
      (node (ref "C24") (pin "2") (pinfunction "2_2") (pintype "passive"))
      (node (ref "U1") (pin "B3") (pinfunction "MGTAVTT_B3") (pintype "passive"))
      (node (ref "U1") (pin "C5") (pinfunction "MGTAVTT_C5") (pintype "passive"))
      (node (ref "U1") (pin "D3") (pinfunction "MGTAVTT_D3") (pintype "passive"))
      (node (ref "U1") (pin "E5") (pinfunction "MGTAVTT_E5") (pintype "passive"))
      (node (ref "U1") (pin "F3") (pinfunction "MGTAVTT_F3") (pintype "passive"))
      (node (ref "U1") (pin "G5") (pinfunction "MGTAVTT_G5") (pintype "passive"))
      (node (ref "U1") (pin "H3") (pinfunction "MGTAVTT_H3") (pintype "passive"))
      (node (ref "U1") (pin "J5") (pinfunction "MGTAVTT_J5") (pintype "passive"))
      (node (ref "U1") (pin "K3") (pinfunction "MGTAVTT_K3") (pintype "passive"))
      (node (ref "U1") (pin "L5") (pinfunction "MGTAVTT_L5") (pintype "passive"))
      (node (ref "U1") (pin "M3") (pinfunction "MGTAVTT_M3") (pintype "passive"))
      (node (ref "U1") (pin "N5") (pinfunction "MGTAVTT_N5") (pintype "passive"))
      (node (ref "U1") (pin "P3") (pinfunction "MGTAVTT_P3") (pintype "passive"))
      (node (ref "U1") (pin "R5") (pinfunction "MGTAVTT_R5") (pintype "passive"))
      (node (ref "U1") (pin "T3") (pinfunction "MGTAVTT_T3") (pintype "passive"))
      (node (ref "U1") (pin "U5") (pinfunction "MGTAVTT_U5") (pintype "passive"))
      (node (ref "U1") (pin "V3") (pinfunction "MGTAVTT_V3") (pintype "passive"))
      (node (ref "U1") (pin "W5") (pinfunction "MGTAVTT_W5") (pintype "passive"))
    )
    (net (code "11") (name "MGT_1.8V") (class "Default")
      (node (ref "C44") (pin "2") (pinfunction "2_2") (pintype "passive"))
      (node (ref "C45") (pin "2") (pinfunction "2_2") (pintype "passive"))
      (node (ref "C46") (pin "2") (pinfunction "2_2") (pintype "passive"))
      (node (ref "C47") (pin "2") (pinfunction "2_2") (pintype "passive"))
      (node (ref "U1") (pin "T7") (pinfunction "MGTVCCAUX_T7") (pintype "passive"))
      (node (ref "U1") (pin "V7") (pinfunction "MGTVCCAUX_V7") (pintype "passive"))
    )
    (net (code "12") (name "VADJ") (class "Default")
      (node (ref "C70") (pin "2") (pinfunction "2_2") (pintype "passive"))
      (node (ref "C71") (pin "2") (pinfunction "2_2") (pintype "passive"))
      (node (ref "U1") (pin "AA29") (pinfunction "VCCO_13_AA29") (pintype "passive"))
      (node (ref "U1") (pin "AB26") (pinfunction "VCCO_13_AB26") (pintype "passive"))
      (node (ref "U1") (pin "AC23") (pinfunction "VCCO_12_AC23") (pintype "passive"))
      (node (ref "U1") (pin "AD20") (pinfunction "VCCO_12_AD20") (pintype "passive"))
      (node (ref "U1") (pin "AD30") (pinfunction "VCCO_13_AD30") (pintype "passive"))
      (node (ref "U1") (pin "AE27") (pinfunction "VCCO_13_AE27") (pintype "passive"))
      (node (ref "U1") (pin "AF24") (pinfunction "VCCO_12_AF24") (pintype "passive"))
      (node (ref "U1") (pin "AG21") (pinfunction "VCCO_12_AG21") (pintype "passive"))
      (node (ref "U1") (pin "AH28") (pinfunction "VCCO_13_AH28") (pintype "passive"))
      (node (ref "U1") (pin "AJ25") (pinfunction "VCCO_13_AJ25") (pintype "passive"))
      (node (ref "U1") (pin "AK22") (pinfunction "VCCO_12_AK22") (pintype "passive"))
      (node (ref "U1") (pin "Y22") (pinfunction "VCCO_12_Y22") (pintype "passive"))
    )
  )
)
